# Helmet_Drop_V2_0.net
KiCad netlist of a schematic drawn in EAGLE
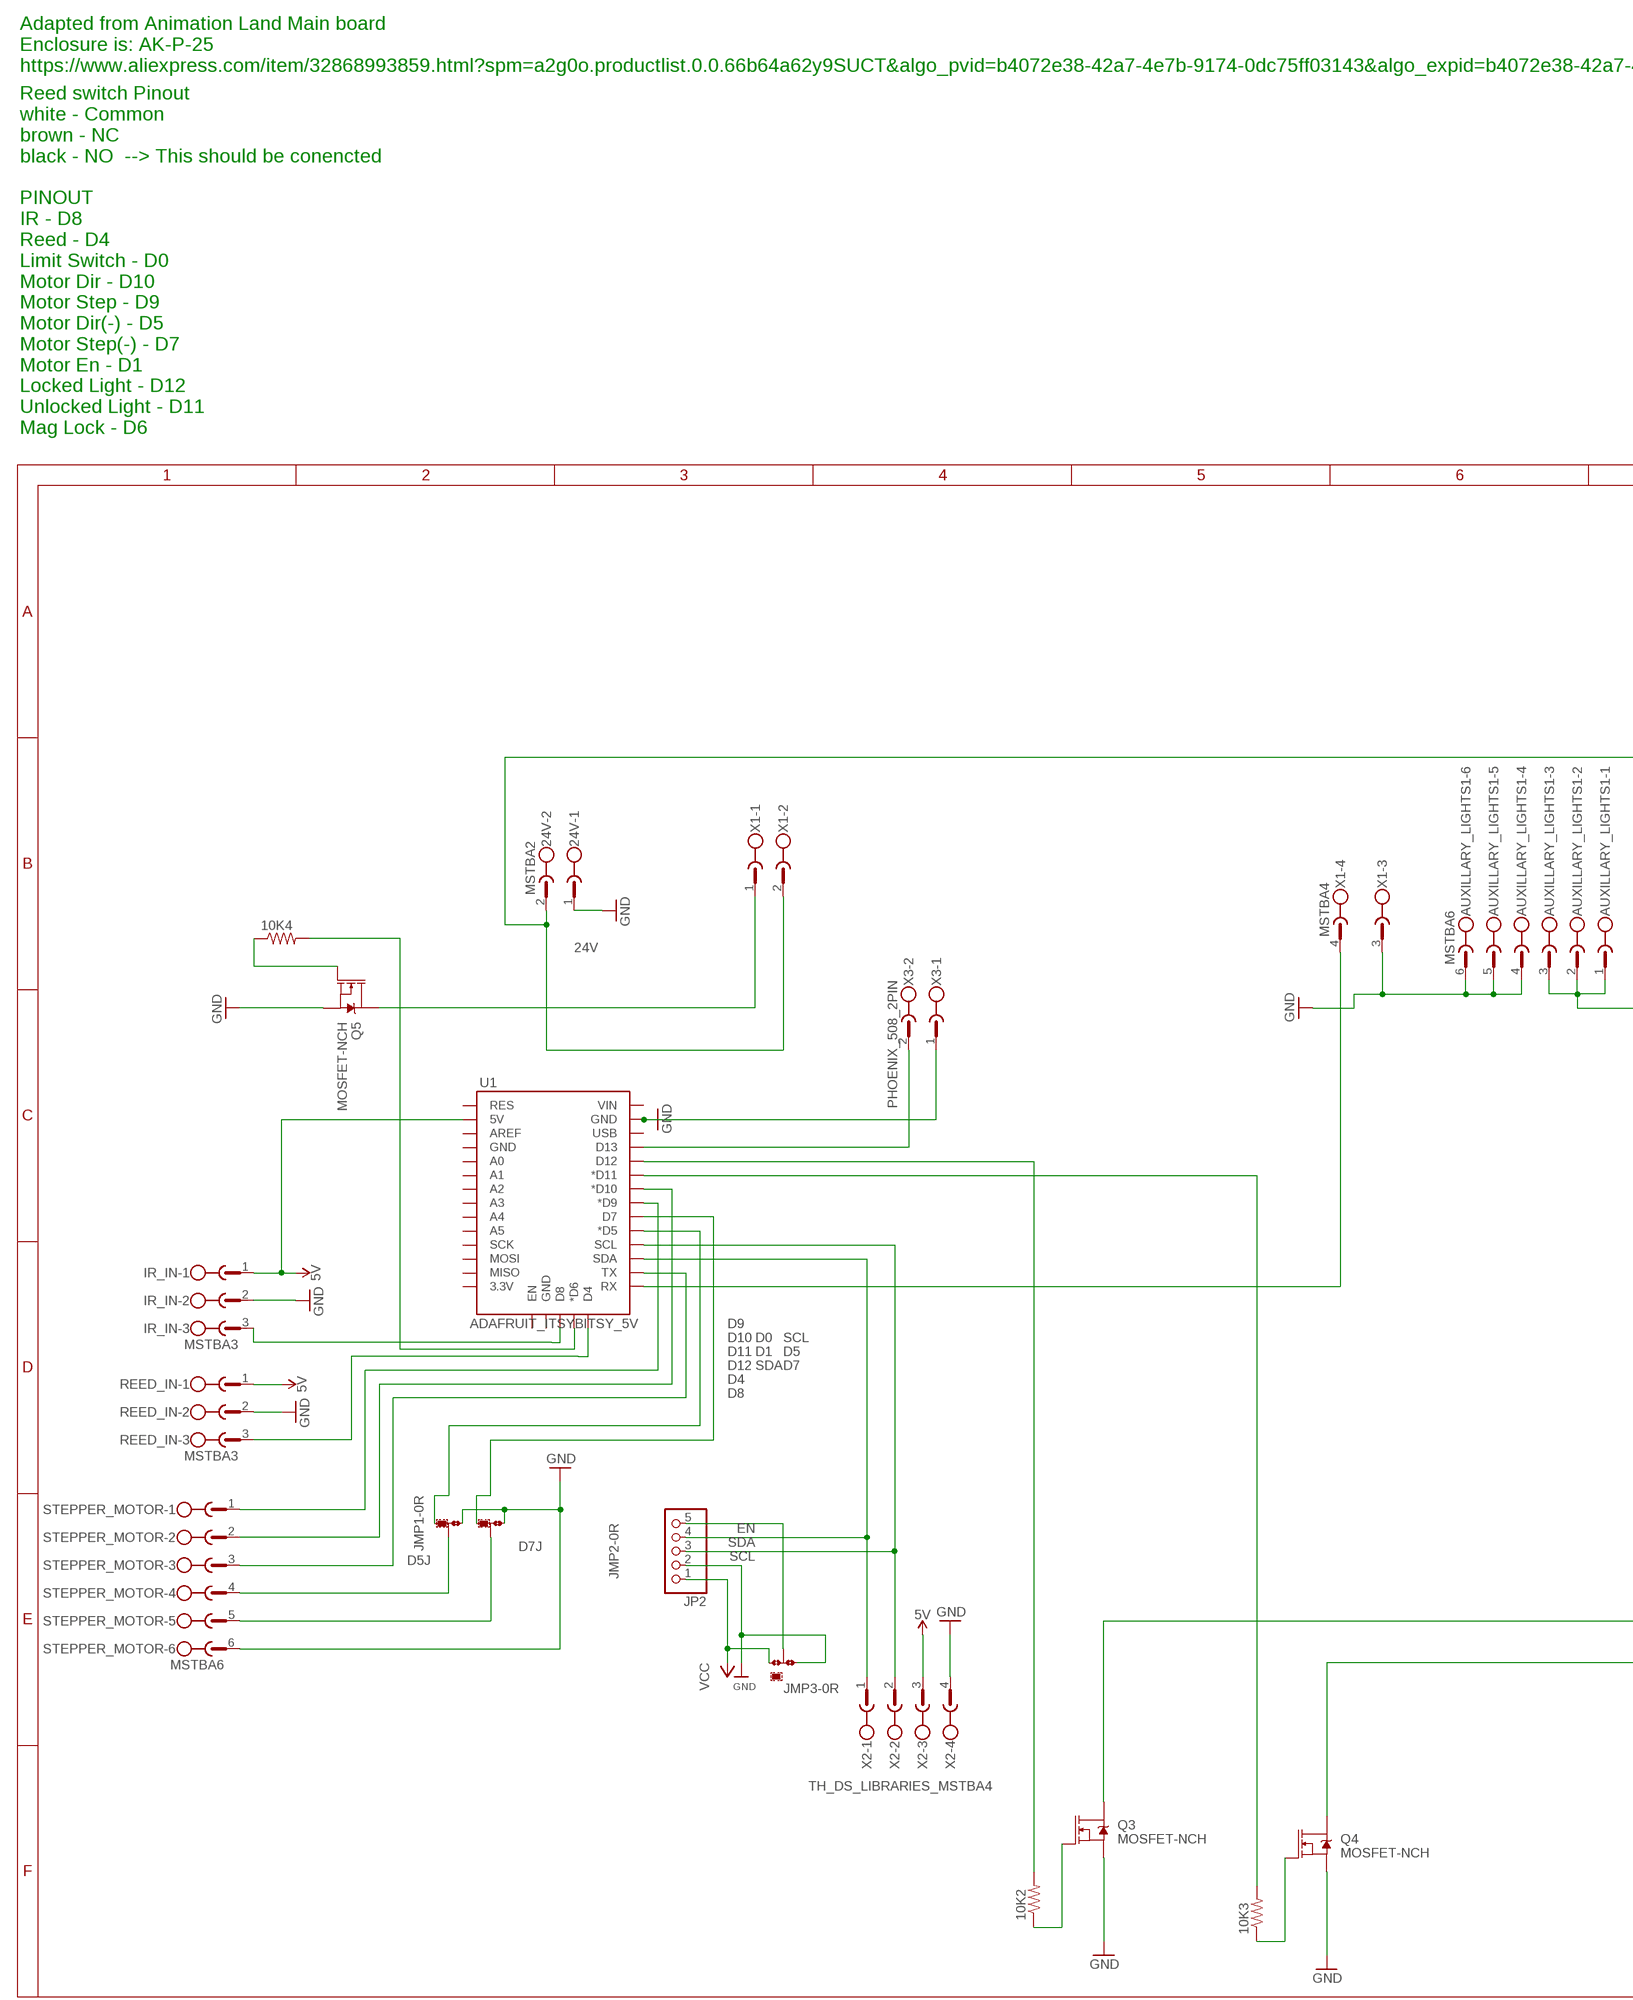
[diagram p0: schematic, sheet 1, part 1 of 2]
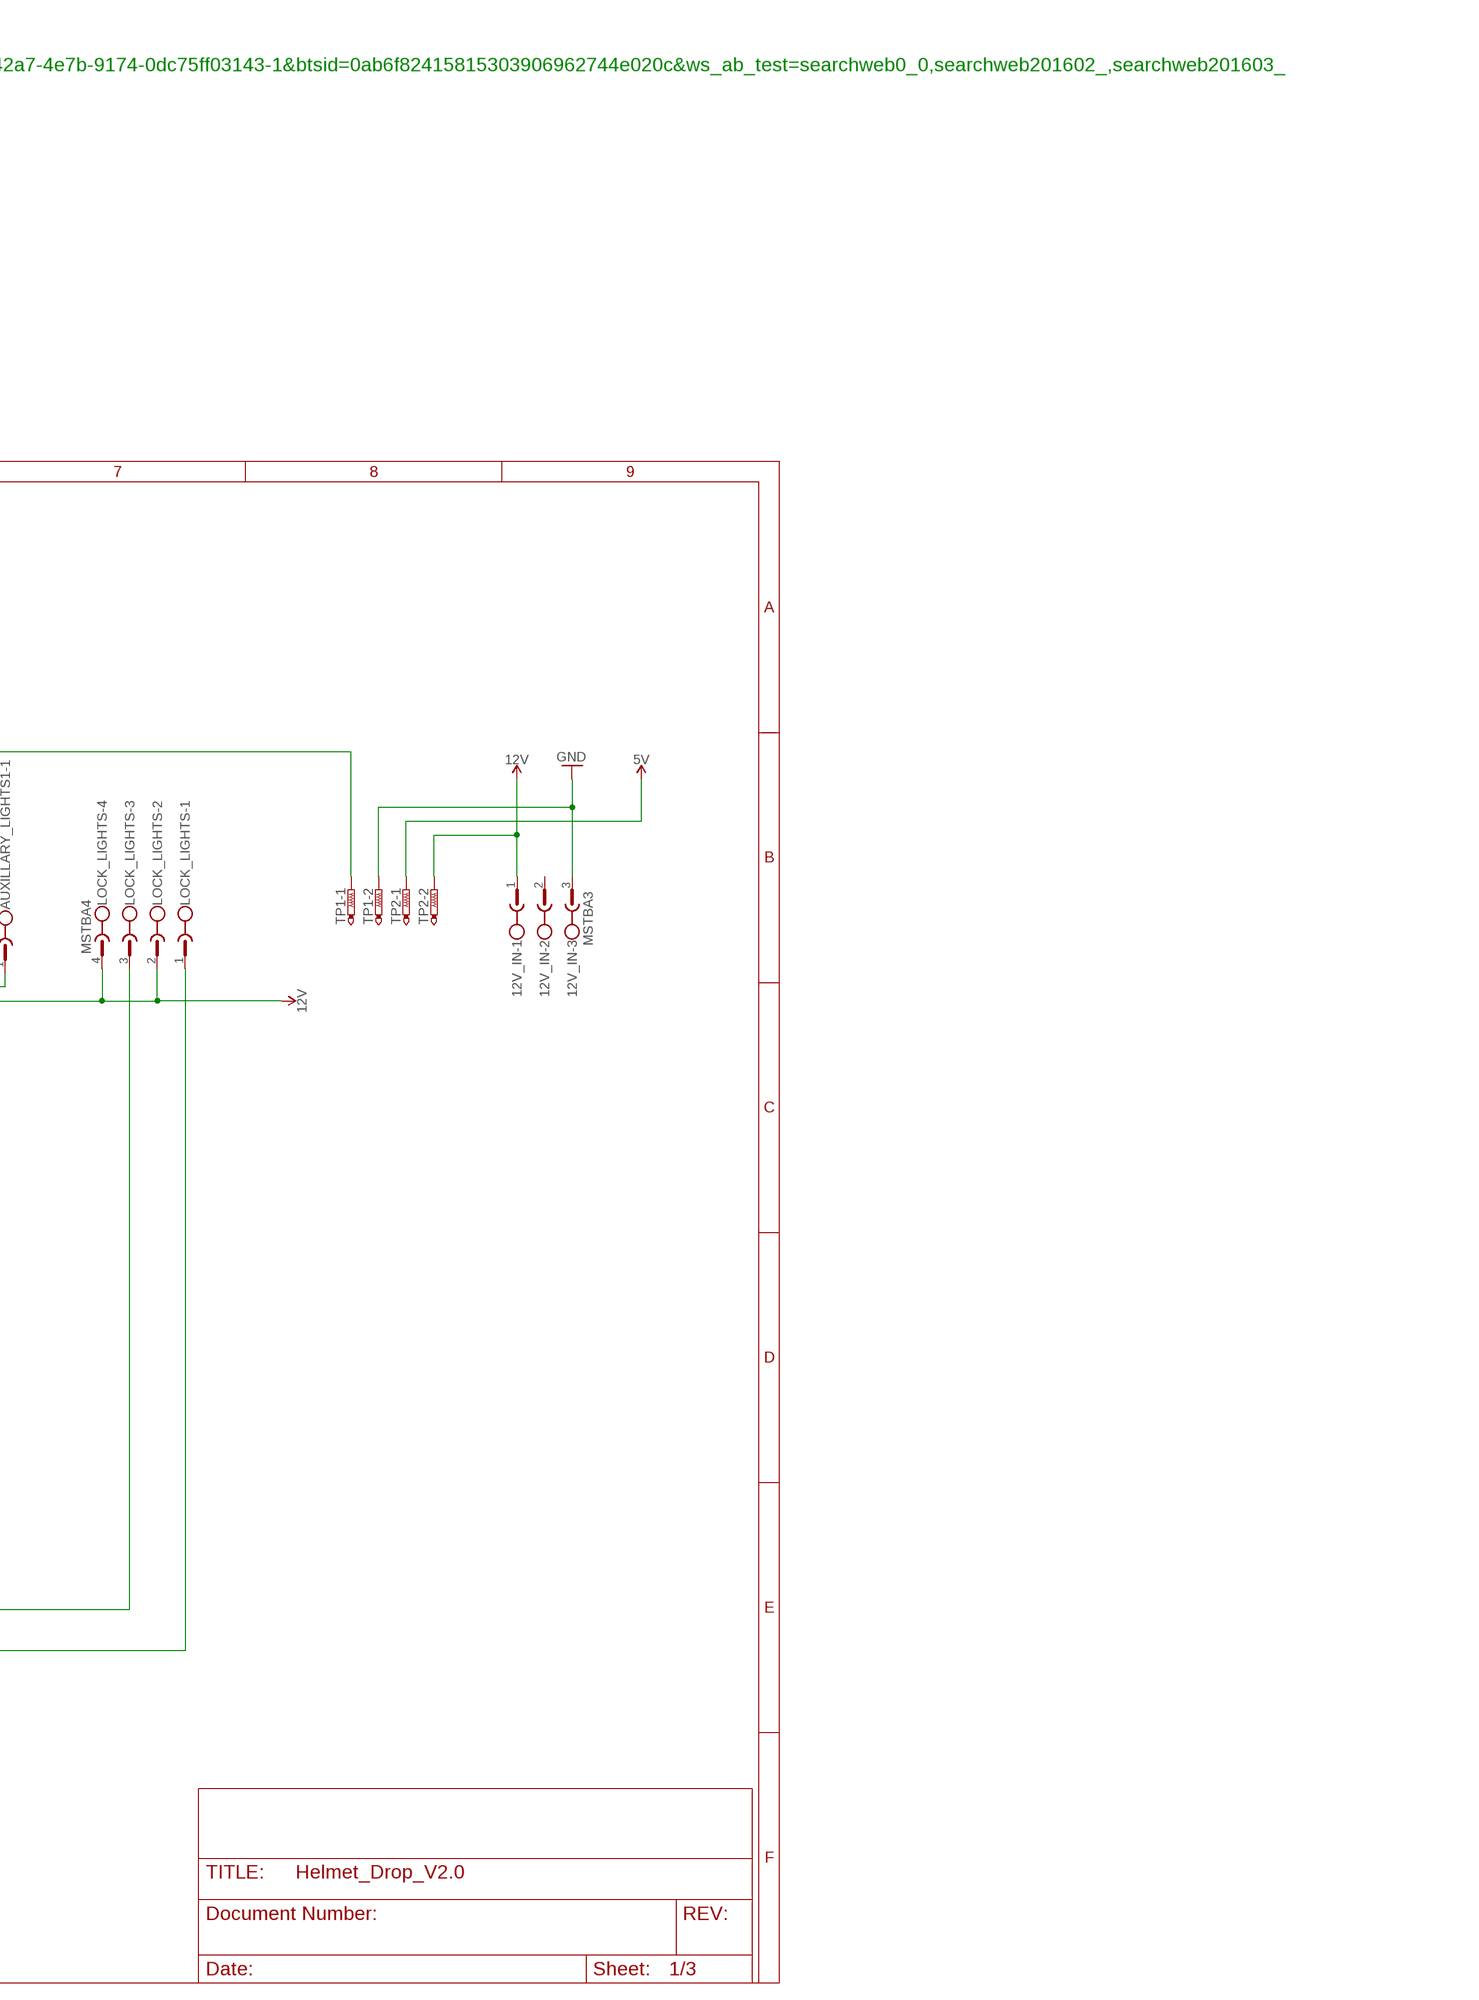
[diagram p1: schematic, sheet 1, part 2 of 2]
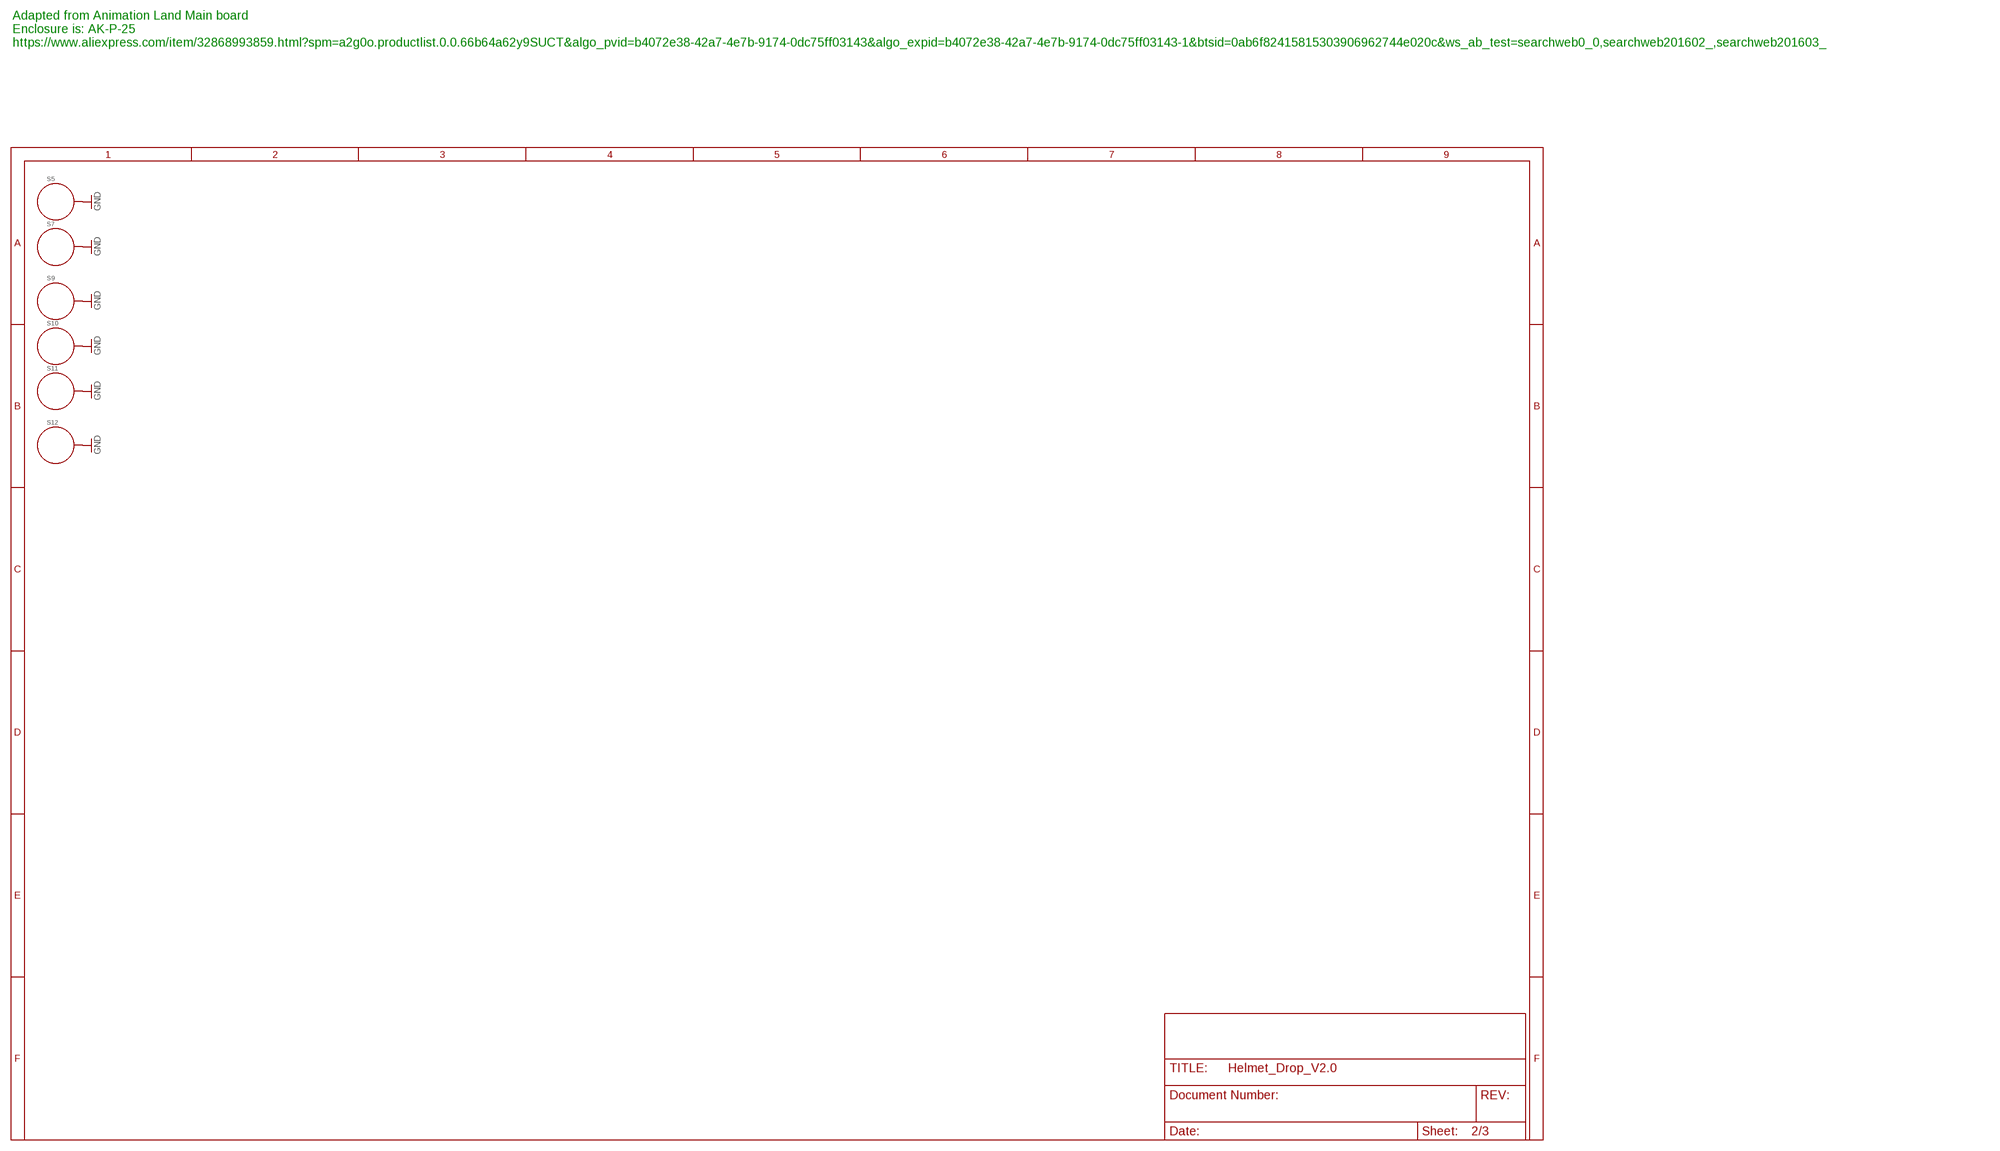
[diagram p2: schematic, sheet 2]
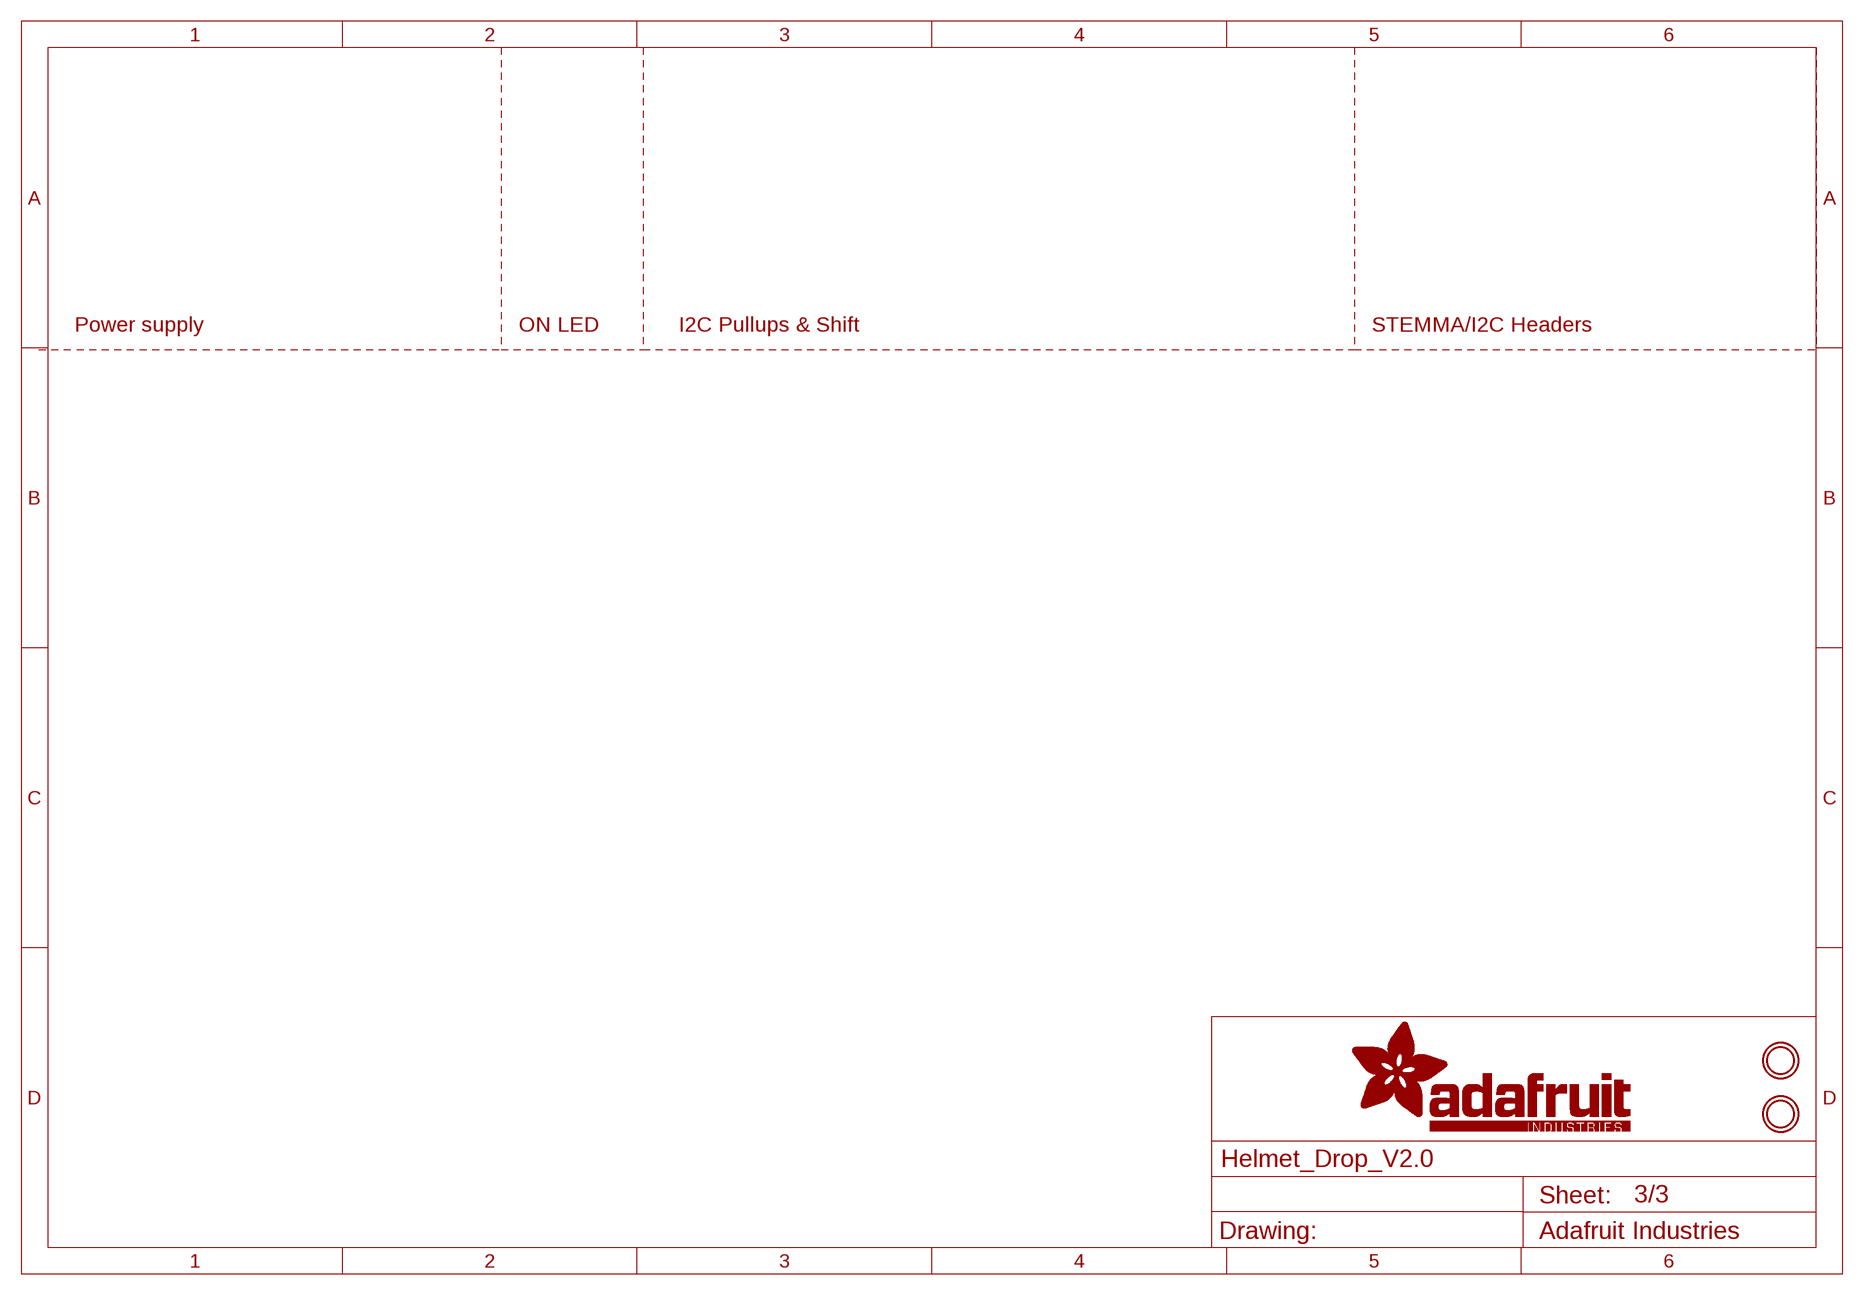
[diagram p3: schematic, sheet 3]

(export (version "E")
  (design (tool "Eeschema 10.0.6"))
  (components
    (comp (ref "10K2")
      (value "R-US_M0805")
      (footprint "eagle-import:M0805")
      (libsource (lib "eagle-import") (part "R-US_M0805"))
    )
    (comp (ref "10K3")
      (value "R-US_M0805")
      (footprint "eagle-import:M0805")
      (libsource (lib "eagle-import") (part "R-US_M0805"))
    )
    (comp (ref "10K4")
      (value "R-US_M0805")
      (footprint "eagle-import:M0805")
      (libsource (lib "eagle-import") (part "R-US_M0805"))
    )
    (comp (ref "12V_IN")
      (value "MSTBA3")
      (footprint "eagle-import:MSTBA3")
      (fields (field (name "MF") "FARNELL") (field (name "MPN") "1757255"))
      (libsource (lib "eagle-import") (part "MSTBA3"))
    )
    (comp (ref "24V")
      (value "MSTBA2")
      (footprint "eagle-import:MSTBA2")
      (fields (field (name "MF") "FARNELL") (field (name "MPN") "1757242"))
      (libsource (lib "eagle-import") (part "MSTBA2"))
    )
    (comp (ref "AUXILLARY_LIGHTS1")
      (value "MSTBA6")
      (footprint "eagle-import:MSTBA6")
      (fields (field (name "MF") "FARNELL") (field (name "MPN") "1757284"))
      (libsource (lib "eagle-import") (part "MSTBA6"))
    )
    (comp (ref "IR_IN")
      (value "MSTBA3")
      (footprint "eagle-import:MSTBA3")
      (fields (field (name "MF") "FARNELL") (field (name "MPN") "1757255"))
      (libsource (lib "eagle-import") (part "MSTBA3"))
    )
    (comp (ref "JMP1")
      (value "0R-JUMPB")
      (footprint "eagle-import:B0R-JMP")
      (libsource (lib "eagle-import") (part "0R-JUMPB"))
    )
    (comp (ref "JMP2")
      (value "0R-JUMPB")
      (footprint "eagle-import:B0R-JMP")
      (libsource (lib "eagle-import") (part "0R-JUMPB"))
    )
    (comp (ref "JMP3")
      (value "0R-JUMPA")
      (footprint "eagle-import:A0R-JMP")
      (libsource (lib "eagle-import") (part "0R-JUMPA"))
    )
    (comp (ref "JP2")
      (value "HEADER-1X570MIL")
      (footprint "eagle-import:1X05_ROUND_70")
      (libsource (lib "eagle-import") (part "HEADER-1X570MIL"))
    )
    (comp (ref "LOCK_LIGHTS")
      (value "MSTBA4")
      (footprint "eagle-import:MSTBA4")
      (fields (field (name "MF") "FARNELL") (field (name "MPN") "1757268"))
      (libsource (lib "eagle-import") (part "th_libraries_26281734_MSTBA4"))
    )
    (comp (ref "Q3")
      (value "MOSFET-NCH")
      (footprint "eagle-import:SO-8_POWER_PAK")
      (libsource (lib "eagle-import") (part "MOSFET-NCH"))
    )
    (comp (ref "Q4")
      (value "MOSFET-NCH")
      (footprint "eagle-import:SO-8_POWER_PAK")
      (libsource (lib "eagle-import") (part "MOSFET-NCH"))
    )
    (comp (ref "Q5")
      (value "MOSFET-NCH")
      (footprint "eagle-import:SO-8_POWER_PAK")
      (libsource (lib "eagle-import") (part "MOSFET-NCH"))
    )
    (comp (ref "REED_IN")
      (value "MSTBA3")
      (footprint "eagle-import:MSTBA3")
      (fields (field (name "MF") "FARNELL") (field (name "MPN") "1757255"))
      (libsource (lib "eagle-import") (part "MSTBA3"))
    )
    (comp (ref "STEPPER_MOTOR")
      (value "MSTBA6")
      (footprint "eagle-import:MSTBA6")
      (fields (field (name "MF") "FARNELL") (field (name "MPN") "1757284"))
      (libsource (lib "eagle-import") (part "MSTBA6"))
    )
    (comp (ref "TP1")
      (value "PTR2")
      (footprint "eagle-import:P2-38-17")
      (libsource (lib "eagle-import") (part "PTR2"))
    )
    (comp (ref "TP2")
      (value "PTR2")
      (footprint "eagle-import:P2-38-17")
      (libsource (lib "eagle-import") (part "PTR2"))
    )
    (comp (ref "U1")
      (value "ADAFRUIT_ITSYBITSY_5V")
      (footprint "eagle-import:ADAFRUIT_ITSYBITSY")
      (libsource (lib "eagle-import") (part "ADAFRUIT_ITSYBITSY_5V"))
    )
    (comp (ref "X1")
      (value "MSTBA4")
      (footprint "eagle-import:MSTBA4")
      (fields (field (name "MF") "FARNELL") (field (name "MPN") "1757268"))
      (libsource (lib "eagle-import") (part "MSTBA4"))
    )
    (comp (ref "X2")
      (value "TH_DS_LIBRARIES_MSTBA4")
      (footprint "eagle-import:TH_DS_LIBRARIES_MSTBA4")
      (fields (field (name "MF") "FARNELL") (field (name "MPN") "1757268"))
      (libsource (lib "eagle-import") (part "TH_DS_LIBRARIES_MSTBA4"))
    )
    (comp (ref "X3")
      (value "PHOENIX_508_2PIN")
      (footprint "eagle-import:PHOENIX_508_2PIN")
      (fields (field (name "MF") "FARNELL") (field (name "MPN") "1757242"))
      (libsource (lib "eagle-import") (part "PHOENIX_508_2PIN"))
    )
    (comp (ref "S5")
      (value "STANDOFF_ELECTRICAL5-32")
      (footprint "eagle-import:STANDOFF_ELECTRICAL_5_32")
      (libsource (lib "eagle-import") (part "STANDOFF_ELECTRICAL5-32"))
    )
    (comp (ref "S7")
      (value "STANDOFF_ELECTRICAL5-32")
      (footprint "eagle-import:STANDOFF_ELECTRICAL_5_32")
      (libsource (lib "eagle-import") (part "STANDOFF_ELECTRICAL5-32"))
    )
    (comp (ref "S9")
      (value "STANDOFF_ELECTRICAL5-32")
      (footprint "eagle-import:STANDOFF_ELECTRICAL_5_32")
      (libsource (lib "eagle-import") (part "STANDOFF_ELECTRICAL5-32"))
    )
    (comp (ref "S10")
      (value "STANDOFF_ELECTRICAL5-32")
      (footprint "eagle-import:STANDOFF_ELECTRICAL_5_32")
      (libsource (lib "eagle-import") (part "STANDOFF_ELECTRICAL5-32"))
    )
    (comp (ref "S11")
      (value "STANDOFF_ELECTRICAL5-32")
      (footprint "eagle-import:STANDOFF_ELECTRICAL_5_32")
      (libsource (lib "eagle-import") (part "STANDOFF_ELECTRICAL5-32"))
    )
    (comp (ref "S12")
      (value "STANDOFF_ELECTRICAL5-32")
      (footprint "eagle-import:STANDOFF_ELECTRICAL_5_32")
      (libsource (lib "eagle-import") (part "STANDOFF_ELECTRICAL5-32"))
    )
    (comp (ref "U$19")
      (value "MOUNTINGHOLE2.5")
      (footprint "eagle-import:MOUNTINGHOLE_2.5_PLATED")
      (libsource (lib "eagle-import") (part "MOUNTINGHOLE2.5"))
    )
    (comp (ref "U$21")
      (value "MOUNTINGHOLE2.5")
      (footprint "eagle-import:MOUNTINGHOLE_2.5_PLATED")
      (libsource (lib "eagle-import") (part "MOUNTINGHOLE2.5"))
    )
  )
  (nets
    (net (code "1") (name "5V") (class "Default")
      (node (ref "IR_IN") (pin "1") (pinfunction "1_1") (pintype "passive"))
      (node (ref "REED_IN") (pin "1") (pinfunction "1_1") (pintype "passive"))
      (node (ref "TP2") (pin "TP-1") (pinfunction "TP_TP-1") (pintype "input"))
      (node (ref "U1") (pin "5V") (pinfunction "5V_5V") (pintype "bidirectional"))
      (node (ref "X2") (pin "3") (pinfunction "1_3") (pintype "passive"))
    )
    (net (code "2") (name "12V") (class "Default")
      (node (ref "12V_IN") (pin "1") (pinfunction "1_1") (pintype "passive"))
      (node (ref "AUXILLARY_LIGHTS1") (pin "1") (pinfunction "1_1") (pintype "passive"))
      (node (ref "AUXILLARY_LIGHTS1") (pin "2") (pinfunction "1_2") (pintype "passive"))
      (node (ref "AUXILLARY_LIGHTS1") (pin "3") (pinfunction "1_3") (pintype "passive"))
      (node (ref "LOCK_LIGHTS") (pin "2") (pinfunction "1_2") (pintype "passive"))
      (node (ref "LOCK_LIGHTS") (pin "4") (pinfunction "1_4") (pintype "passive"))
      (node (ref "TP2") (pin "TP-2") (pinfunction "TP_TP-2") (pintype "input"))
    )
    (net (code "3") (name "24V") (class "Default")
      (node (ref "24V") (pin "2") (pinfunction "1_2") (pintype "passive"))
      (node (ref "TP1") (pin "TP-1") (pinfunction "TP_TP-1") (pintype "input"))
      (node (ref "X1") (pin "2") (pinfunction "1_2") (pintype "passive"))
    )
    (net (code "4") (name "D0") (class "Default")
      (node (ref "U1") (pin "RX") (pinfunction "RX_RX") (pintype "bidirectional"))
      (node (ref "X1") (pin "4") (pinfunction "1_4") (pintype "passive"))
    )
    (net (code "5") (name "D1") (class "Default")
      (node (ref "STEPPER_MOTOR") (pin "3") (pinfunction "1_3") (pintype "passive"))
      (node (ref "U1") (pin "TX") (pinfunction "TX_TX") (pintype "bidirectional"))
    )
    (net (code "6") (name "D4") (class "Default")
      (node (ref "REED_IN") (pin "3") (pinfunction "1_3") (pintype "passive"))
      (node (ref "U1") (pin "D4") (pinfunction "D4_D4") (pintype "bidirectional"))
    )
    (net (code "7") (name "D5") (class "Default")
      (node (ref "JMP1") (pin "3") (pinfunction "3_3") (pintype "passive"))
      (node (ref "U1") (pin "D5") (pinfunction "*D5_D5") (pintype "bidirectional"))
    )
    (net (code "8") (name "D5J") (class "Default")
      (node (ref "JMP1") (pin "2") (pinfunction "2_2") (pintype "passive"))
      (node (ref "STEPPER_MOTOR") (pin "4") (pinfunction "1_4") (pintype "passive"))
    )
    (net (code "9") (name "D7") (class "Default")
      (node (ref "JMP2") (pin "3") (pinfunction "3_3") (pintype "passive"))
      (node (ref "U1") (pin "D7") (pinfunction "D7_D7") (pintype "bidirectional"))
    )
    (net (code "10") (name "D7J") (class "Default")
      (node (ref "JMP2") (pin "2") (pinfunction "2_2") (pintype "passive"))
      (node (ref "STEPPER_MOTOR") (pin "5") (pinfunction "1_5") (pintype "passive"))
    )
    (net (code "11") (name "D8") (class "Default")
      (node (ref "IR_IN") (pin "3") (pinfunction "1_3") (pintype "passive"))
      (node (ref "U1") (pin "D8") (pinfunction "D8_D8") (pintype "bidirectional"))
    )
    (net (code "12") (name "D9") (class "Default")
      (node (ref "STEPPER_MOTOR") (pin "1") (pinfunction "1_1") (pintype "passive"))
      (node (ref "U1") (pin "D9") (pinfunction "*D9_D9") (pintype "bidirectional"))
    )
    (net (code "13") (name "D10") (class "Default")
      (node (ref "STEPPER_MOTOR") (pin "2") (pinfunction "1_2") (pintype "passive"))
      (node (ref "U1") (pin "D10") (pinfunction "*D10_D10") (pintype "bidirectional"))
    )
    (net (code "14") (name "D11") (class "Default")
      (node (ref "10K3") (pin "2") (pinfunction "2_2") (pintype "passive"))
      (node (ref "U1") (pin "D11") (pinfunction "*D11_D11") (pintype "bidirectional"))
    )
    (net (code "15") (name "D12") (class "Default")
      (node (ref "10K2") (pin "2") (pinfunction "2_2") (pintype "passive"))
      (node (ref "U1") (pin "D12") (pinfunction "D12_D12") (pintype "bidirectional"))
    )
    (net (code "16") (name "EN") (class "Default")
      (node (ref "JMP3") (pin "2") (pinfunction "2_2") (pintype "passive"))
      (node (ref "JP2") (pin "5") (pinfunction "5_5") (pintype "passive"))
    )
    (net (code "17") (name "GND") (class "Default")
      (node (ref "12V_IN") (pin "3") (pinfunction "1_3") (pintype "passive"))
      (node (ref "24V") (pin "1") (pinfunction "1_1") (pintype "passive"))
      (node (ref "AUXILLARY_LIGHTS1") (pin "4") (pinfunction "1_4") (pintype "passive"))
      (node (ref "AUXILLARY_LIGHTS1") (pin "5") (pinfunction "1_5") (pintype "passive"))
      (node (ref "AUXILLARY_LIGHTS1") (pin "6") (pinfunction "1_6") (pintype "passive"))
      (node (ref "IR_IN") (pin "2") (pinfunction "1_2") (pintype "passive"))
      (node (ref "JMP1") (pin "1") (pinfunction "1_1") (pintype "passive"))
      (node (ref "JMP2") (pin "1") (pinfunction "1_1") (pintype "passive"))
      (node (ref "JMP3") (pin "3") (pinfunction "3_3") (pintype "passive"))
      (node (ref "JP2") (pin "2") (pinfunction "2_2") (pintype "passive"))
      (node (ref "Q3") (pin "S") (pinfunction "S_S") (pintype "bidirectional"))
      (node (ref "Q4") (pin "S") (pinfunction "S_S") (pintype "bidirectional"))
      (node (ref "Q5") (pin "S") (pinfunction "S_S") (pintype "bidirectional"))
      (node (ref "REED_IN") (pin "2") (pinfunction "1_2") (pintype "passive"))
      (node (ref "S10") (pin "P1") (pinfunction "P$1_P1") (pintype "bidirectional"))
      (node (ref "S11") (pin "P1") (pinfunction "P$1_P1") (pintype "bidirectional"))
      (node (ref "S12") (pin "P1") (pinfunction "P$1_P1") (pintype "bidirectional"))
      (node (ref "S5") (pin "P1") (pinfunction "P$1_P1") (pintype "bidirectional"))
      (node (ref "S7") (pin "P1") (pinfunction "P$1_P1") (pintype "bidirectional"))
      (node (ref "S9") (pin "P1") (pinfunction "P$1_P1") (pintype "bidirectional"))
      (node (ref "STEPPER_MOTOR") (pin "6") (pinfunction "1_6") (pintype "passive"))
      (node (ref "TP1") (pin "TP-2") (pinfunction "TP_TP-2") (pintype "input"))
      (node (ref "U1") (pin "GND@2") (pinfunction "GND_GND@2") (pintype "bidirectional"))
      (node (ref "X1") (pin "3") (pinfunction "1_3") (pintype "passive"))
      (node (ref "X2") (pin "4") (pinfunction "1_4") (pintype "passive"))
      (node (ref "X3") (pin "1") (pinfunction "1_1") (pintype "passive"))
    )
    (net (code "18") (name "Net-(10K2-Pad1)") (class "Default")
      (node (ref "10K2") (pin "1") (pinfunction "1_1") (pintype "passive"))
      (node (ref "Q3") (pin "G") (pinfunction "G_G") (pintype "bidirectional"))
    )
    (net (code "19") (name "Net-(10K3-Pad1)") (class "Default")
      (node (ref "10K3") (pin "1") (pinfunction "1_1") (pintype "passive"))
      (node (ref "Q4") (pin "G") (pinfunction "G_G") (pintype "bidirectional"))
    )
    (net (code "20") (name "Net-(10K4-Pad1)") (class "Default")
      (node (ref "10K4") (pin "1") (pinfunction "1_1") (pintype "passive"))
      (node (ref "Q5") (pin "G") (pinfunction "G_G") (pintype "bidirectional"))
    )
    (net (code "21") (name "Net-(LOCK_LIGHTSC-1)") (class "Default")
      (node (ref "LOCK_LIGHTS") (pin "3") (pinfunction "1_3") (pintype "passive"))
      (node (ref "Q3") (pin "D1") (pinfunction "D_D1") (pintype "bidirectional"))
    )
    (net (code "22") (name "Net-(Q4-D)") (class "Default")
      (node (ref "LOCK_LIGHTS") (pin "1") (pinfunction "1_1") (pintype "passive"))
      (node (ref "Q4") (pin "D1") (pinfunction "D_D1") (pintype "bidirectional"))
    )
    (net (code "23") (name "Net-(Q5-D)") (class "Default")
      (node (ref "Q5") (pin "D1") (pinfunction "D_D1") (pintype "bidirectional"))
      (node (ref "X1") (pin "1") (pinfunction "1_1") (pintype "passive"))
    )
    (net (code "24") (name "Net-(U1-*D6)") (class "Default")
      (node (ref "10K4") (pin "2") (pinfunction "2_2") (pintype "passive"))
      (node (ref "U1") (pin "D6") (pinfunction "*D6_D6") (pintype "bidirectional"))
    )
    (net (code "25") (name "Net-(X3B-1)") (class "Default")
      (node (ref "U1") (pin "D13") (pinfunction "D13_D13") (pintype "bidirectional"))
      (node (ref "X3") (pin "2") (pinfunction "1_2") (pintype "passive"))
    )
    (net (code "26") (name "SCL") (class "Default")
      (node (ref "JP2") (pin "3") (pinfunction "3_3") (pintype "passive"))
      (node (ref "U1") (pin "SCL") (pinfunction "SCL_SCL") (pintype "bidirectional"))
      (node (ref "X2") (pin "2") (pinfunction "1_2") (pintype "passive"))
    )
    (net (code "27") (name "SDA") (class "Default")
      (node (ref "JP2") (pin "4") (pinfunction "4_4") (pintype "passive"))
      (node (ref "U1") (pin "SDA") (pinfunction "SDA_SDA") (pintype "bidirectional"))
      (node (ref "X2") (pin "1") (pinfunction "1_1") (pintype "passive"))
    )
    (net (code "28") (name "VCC") (class "Default")
      (node (ref "JMP3") (pin "1") (pinfunction "1_1") (pintype "passive"))
      (node (ref "JP2") (pin "1") (pinfunction "1_1") (pintype "passive"))
    )
    (net (code "29") (name "unconnected-(12V_INB-1-Pad2)") (class "Default")
      (node (ref "12V_IN") (pin "2") (pinfunction "1_2") (pintype "passive"))
    )
    (net (code "30") (name "unconnected-(U1-3.3V-Pad3V)") (class "Default")
      (node (ref "U1") (pin "3V") (pinfunction "3.3V_3V") (pintype "bidirectional"))
    )
    (net (code "31") (name "unconnected-(U1-GND-PadGND@0)") (class "Default")
      (node (ref "U1") (pin "GND@0") (pinfunction "GND_GND@0") (pintype "bidirectional"))
    )
    (net (code "32") (name "unconnected-(U1-GND-PadGND@1)") (class "Default")
      (node (ref "U1") (pin "GND@1") (pinfunction "GND_GND@1") (pintype "bidirectional"))
    )
    (net (code "33") (name "unconnected-(U1-PadA0)") (class "Default")
      (node (ref "U1") (pin "A0") (pinfunction "A0_A0") (pintype "bidirectional"))
    )
    (net (code "34") (name "unconnected-(U1-PadA1)") (class "Default")
      (node (ref "U1") (pin "A1") (pinfunction "A1_A1") (pintype "bidirectional"))
    )
    (net (code "35") (name "unconnected-(U1-PadA2)") (class "Default")
      (node (ref "U1") (pin "A2") (pinfunction "A2_A2") (pintype "bidirectional"))
    )
    (net (code "36") (name "unconnected-(U1-PadA3)") (class "Default")
      (node (ref "U1") (pin "A3") (pinfunction "A3_A3") (pintype "bidirectional"))
    )
    (net (code "37") (name "unconnected-(U1-PadA4)") (class "Default")
      (node (ref "U1") (pin "A4") (pinfunction "A4_A4") (pintype "bidirectional"))
    )
    (net (code "38") (name "unconnected-(U1-PadA5)") (class "Default")
      (node (ref "U1") (pin "A5") (pinfunction "A5_A5") (pintype "bidirectional"))
    )
    (net (code "39") (name "unconnected-(U1-PadAREF)") (class "Default")
      (node (ref "U1") (pin "AREF") (pinfunction "AREF_AREF") (pintype "bidirectional"))
    )
    (net (code "40") (name "unconnected-(U1-PadEN)") (class "Default")
      (node (ref "U1") (pin "EN") (pinfunction "EN_EN") (pintype "bidirectional"))
    )
    (net (code "41") (name "unconnected-(U1-PadMISO)") (class "Default")
      (node (ref "U1") (pin "MISO") (pinfunction "MISO_MISO") (pintype "bidirectional"))
    )
    (net (code "42") (name "unconnected-(U1-PadMOSI)") (class "Default")
      (node (ref "U1") (pin "MOSI") (pinfunction "MOSI_MOSI") (pintype "bidirectional"))
    )
    (net (code "43") (name "unconnected-(U1-PadRES)") (class "Default")
      (node (ref "U1") (pin "RES") (pinfunction "RES_RES") (pintype "bidirectional"))
    )
    (net (code "44") (name "unconnected-(U1-PadSCK)") (class "Default")
      (node (ref "U1") (pin "SCK") (pinfunction "SCK_SCK") (pintype "bidirectional"))
    )
    (net (code "45") (name "unconnected-(U1-PadUSB)") (class "Default")
      (node (ref "U1") (pin "USB") (pinfunction "USB_USB") (pintype "bidirectional"))
    )
    (net (code "46") (name "unconnected-(U1-PadVIN)") (class "Default")
      (node (ref "U1") (pin "VIN") (pinfunction "VIN_VIN") (pintype "bidirectional"))
    )
  )
)
